# Input_-_Pedals.net
KiCad netlist of a schematic drawn in Altium Designer
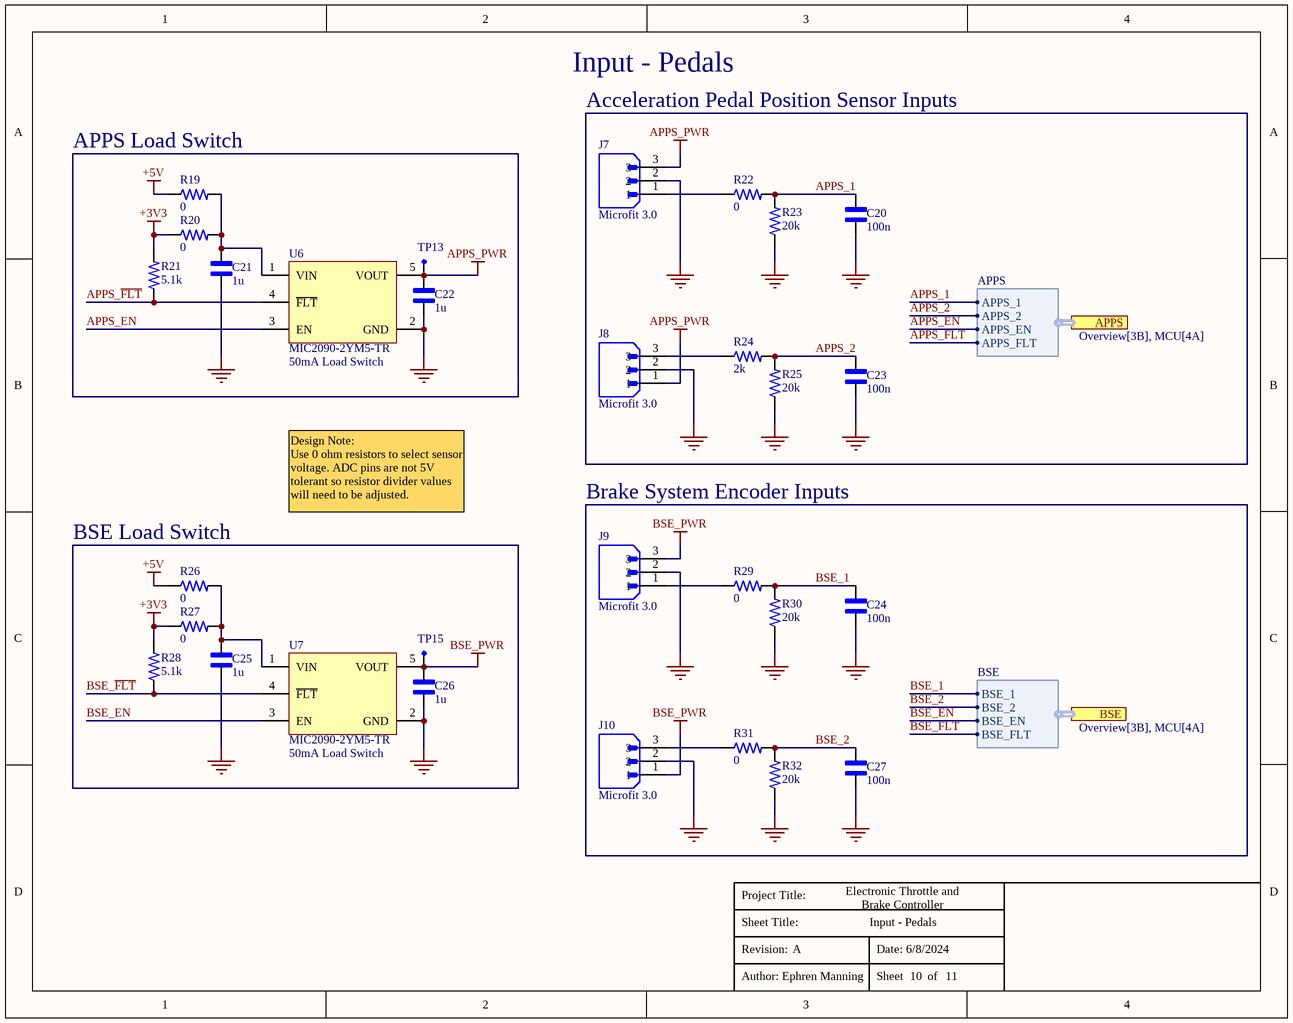
[diagram p0: Input - Pedals.SchDoc]

(export (version "E")
  (design (tool "Eeschema 10.0.6"))
  (components
    (comp (ref "C20")
      (value "100n")
      (footprint "CAP_0402-Footprint-1")
      (description "100nF 10V 10% 0402 CAP")
      (fields (field (name "DIGIKEY PART NUMBER") "1276-1002-1-ND"))
      (libsource (lib "SAE @ UIC Formula Electric") (part "CAP_0402-Symbol-1"))
    )
    (comp (ref "C21")
      (value "1u")
      (footprint "CAP_0402-Footprint-1")
      (description "1uF 10V 10% 0402 CAP")
      (fields (field (name "DIGIKEY PART NUMBER") "1276-1076-1-ND"))
      (libsource (lib "SAE @ UIC Formula Electric") (part "CAP_0402-Symbol-1"))
    )
    (comp (ref "C22")
      (value "1u")
      (footprint "CAP_0402-Footprint-1")
      (description "1uF 10V 10% 0402 CAP")
      (fields (field (name "DIGIKEY PART NUMBER") "1276-1076-1-ND"))
      (libsource (lib "SAE @ UIC Formula Electric") (part "CAP_0402-Symbol-1"))
    )
    (comp (ref "C23")
      (value "100n")
      (footprint "CAP_0402-Footprint-1")
      (description "100nF 10V 10% 0402 CAP")
      (fields (field (name "DIGIKEY PART NUMBER") "1276-1002-1-ND"))
      (libsource (lib "SAE @ UIC Formula Electric") (part "CAP_0402-Symbol-1"))
    )
    (comp (ref "C24")
      (value "100n")
      (footprint "CAP_0402-Footprint-1")
      (description "100nF 10V 10% 0402 CAP")
      (fields (field (name "DIGIKEY PART NUMBER") "1276-1002-1-ND"))
      (libsource (lib "SAE @ UIC Formula Electric") (part "CAP_0402-Symbol-1"))
    )
    (comp (ref "C25")
      (value "1u")
      (footprint "CAP_0402-Footprint-1")
      (description "1uF 10V 10% 0402 CAP")
      (fields (field (name "DIGIKEY PART NUMBER") "1276-1076-1-ND"))
      (libsource (lib "SAE @ UIC Formula Electric") (part "CAP_0402-Symbol-1"))
    )
    (comp (ref "C26")
      (value "1u")
      (footprint "CAP_0402-Footprint-1")
      (description "1uF 10V 10% 0402 CAP")
      (fields (field (name "DIGIKEY PART NUMBER") "1276-1076-1-ND"))
      (libsource (lib "SAE @ UIC Formula Electric") (part "CAP_0402-Symbol-1"))
    )
    (comp (ref "C27")
      (value "100n")
      (footprint "CAP_0402-Footprint-1")
      (description "100nF 10V 10% 0402 CAP")
      (fields (field (name "DIGIKEY PART NUMBER") "1276-1002-1-ND"))
      (libsource (lib "SAE @ UIC Formula Electric") (part "CAP_0402-Symbol-1"))
    )
    (comp (ref "J7")
      (value "Microfit 3.0")
      (footprint "MOLEX_436500316")
      (description "1x3 Gold Microfit")
      (fields (field (name "DIGIKEY PART NUMBER") "WM1923-ND"))
      (libsource (lib "SAE @ UIC Formula Electric") (part "436500316"))
    )
    (comp (ref "J8")
      (value "Microfit 3.0")
      (footprint "MOLEX_436500316")
      (description "1x3 Gold Microfit")
      (fields (field (name "DIGIKEY PART NUMBER") "WM1923-ND"))
      (libsource (lib "SAE @ UIC Formula Electric") (part "436500316"))
    )
    (comp (ref "J9")
      (value "Microfit 3.0")
      (footprint "MOLEX_436500316")
      (description "1x3 Gold Microfit")
      (fields (field (name "DIGIKEY PART NUMBER") "WM1923-ND"))
      (libsource (lib "SAE @ UIC Formula Electric") (part "436500316"))
    )
    (comp (ref "J10")
      (value "Microfit 3.0")
      (footprint "MOLEX_436500316")
      (description "1x3 Gold Microfit")
      (fields (field (name "DIGIKEY PART NUMBER") "WM1923-ND"))
      (libsource (lib "SAE @ UIC Formula Electric") (part "436500316"))
    )
    (comp (ref "R19")
      (value "0")
      (footprint "RES_0402-Footprint-1")
      (description "0 Ohm 1/16W 0402 Resistor")
      (fields (field (name "DIGIKEY PART NUMBER") "311-0.0JRCT-ND"))
      (libsource (lib "SAE @ UIC Formula Electric") (part "RES_0402_Symbol"))
    )
    (comp (ref "R20")
      (value "0")
      (footprint "RES_0402-Footprint-1")
      (description "0 Ohm 1/16W 0402 Resistor")
      (fields (field (name "DIGIKEY PART NUMBER") "311-0.0JRCT-ND"))
      (libsource (lib "SAE @ UIC Formula Electric") (part "RES_0402_Symbol"))
    )
    (comp (ref "R21")
      (value "5.1k")
      (footprint "RES_0402-Footprint-1")
      (description "5.1k 1% 1/16W 0402 Resistor")
      (fields (field (name "DIGIKEY PART NUMBER") "311-5.10KLRCT-ND"))
      (libsource (lib "SAE @ UIC Formula Electric") (part "RES_0402_Symbol"))
    )
    (comp (ref "R22")
      (value "0")
      (footprint "RES_0402-Footprint-1")
      (description "0 Ohm 1/16W 0402 Resistor")
      (fields (field (name "DIGIKEY PART NUMBER") "311-0.0JRCT-ND"))
      (libsource (lib "SAE @ UIC Formula Electric") (part "RES_0402_Symbol"))
    )
    (comp (ref "R23")
      (value "20k")
      (footprint "RES_0402-Footprint-1")
      (description "20k 0.1% 1/16W 0402 Thin Film")
      (fields (field (name "DIGIKEY PART NUMBER") "YAG1388CT-ND"))
      (libsource (lib "SAE @ UIC Formula Electric") (part "RES_0402_Symbol"))
    )
    (comp (ref "R24")
      (value "2k")
      (footprint "RES_0402-Footprint-1")
      (description "2k 0.1% 1/16W 0402 Thin Film")
      (fields (field (name "DIGIKEY PART NUMBER") "YAG2303CT-ND"))
      (libsource (lib "SAE @ UIC Formula Electric") (part "RES_0402_Symbol"))
    )
    (comp (ref "R25")
      (value "20k")
      (footprint "RES_0402-Footprint-1")
      (description "20k 0.1% 1/16W 0402 Thin Film")
      (fields (field (name "DIGIKEY PART NUMBER") "YAG1388CT-ND"))
      (libsource (lib "SAE @ UIC Formula Electric") (part "RES_0402_Symbol"))
    )
    (comp (ref "R26")
      (value "0")
      (footprint "RES_0402-Footprint-1")
      (description "0 Ohm 1/16W 0402 Resistor")
      (fields (field (name "DIGIKEY PART NUMBER") "311-0.0JRCT-ND"))
      (libsource (lib "SAE @ UIC Formula Electric") (part "RES_0402_Symbol"))
    )
    (comp (ref "R27")
      (value "0")
      (footprint "RES_0402-Footprint-1")
      (description "0 Ohm 1/16W 0402 Resistor")
      (fields (field (name "DIGIKEY PART NUMBER") "311-0.0JRCT-ND"))
      (libsource (lib "SAE @ UIC Formula Electric") (part "RES_0402_Symbol"))
    )
    (comp (ref "R28")
      (value "5.1k")
      (footprint "RES_0402-Footprint-1")
      (description "5.1k 1% 1/16W 0402 Resistor")
      (fields (field (name "DIGIKEY PART NUMBER") "311-5.10KLRCT-ND"))
      (libsource (lib "SAE @ UIC Formula Electric") (part "RES_0402_Symbol"))
    )
    (comp (ref "R29")
      (value "0")
      (footprint "RES_0402-Footprint-1")
      (description "0 Ohm 1/16W 0402 Resistor")
      (fields (field (name "DIGIKEY PART NUMBER") "311-0.0JRCT-ND"))
      (libsource (lib "SAE @ UIC Formula Electric") (part "RES_0402_Symbol"))
    )
    (comp (ref "R30")
      (value "20k")
      (footprint "RES_0402-Footprint-1")
      (description "20k 0.1% 1/16W 0402 Thin Film")
      (fields (field (name "DIGIKEY PART NUMBER") "YAG1388CT-ND"))
      (libsource (lib "SAE @ UIC Formula Electric") (part "RES_0402_Symbol"))
    )
    (comp (ref "R31")
      (value "0")
      (footprint "RES_0402-Footprint-1")
      (description "0 Ohm 1/16W 0402 Resistor")
      (fields (field (name "DIGIKEY PART NUMBER") "311-0.0JRCT-ND"))
      (libsource (lib "SAE @ UIC Formula Electric") (part "RES_0402_Symbol"))
    )
    (comp (ref "R32")
      (value "20k")
      (footprint "RES_0402-Footprint-1")
      (description "20k 0.1% 1/16W 0402 Thin Film")
      (fields (field (name "DIGIKEY PART NUMBER") "YAG1388CT-ND"))
      (libsource (lib "SAE @ UIC Formula Electric") (part "RES_0402_Symbol"))
    )
    (comp (ref "TP13")
      (value "SMD Testpoint")
      (footprint "SMD Testpoint-Footprint-1")
      (description "Flat 50x50mil Test Point")
      (libsource (lib "SAE @ UIC Formula Electric") (part "SMD Testpoint-Symbol-1"))
    )
    (comp (ref "TP15")
      (value "SMD Testpoint")
      (footprint "SMD Testpoint-Footprint-1")
      (description "Flat 50x50mil Test Point")
      (libsource (lib "SAE @ UIC Formula Electric") (part "SMD Testpoint-Symbol-1"))
    )
    (comp (ref "U6")
      (value "MIC2090-2YM5-TR")
      (footprint "SOT95P275X110-5N")
      (description "50mA Load Switch w/ Overcurrent Protection")
      (fields (field (name "DIGIKEY PART NUMBER") "576-3964-1-ND"))
      (libsource (lib "SAE @ UIC Formula Electric") (part "MIC2090-2YM5-TR-Symbol-1"))
    )
    (comp (ref "U7")
      (value "MIC2090-2YM5-TR")
      (footprint "SOT95P275X110-5N")
      (description "50mA Load Switch w/ Overcurrent Protection")
      (fields (field (name "DIGIKEY PART NUMBER") "576-3964-1-ND"))
      (libsource (lib "SAE @ UIC Formula Electric") (part "MIC2090-2YM5-TR-Symbol-1"))
    )
  )
  (nets
    (net (code "3") (name "+3V3") (class "Default")
      (node (ref "R20") (pin "1") (pinfunction "1_1") (pintype "passive"))
      (node (ref "R21") (pin "2") (pinfunction "2_2") (pintype "passive"))
      (node (ref "R27") (pin "1") (pinfunction "1_1") (pintype "passive"))
      (node (ref "R28") (pin "2") (pinfunction "2_2") (pintype "passive"))
    )
    (net (code "4") (name "+5V") (class "Default")
      (node (ref "R19") (pin "1") (pinfunction "1_1") (pintype "passive"))
      (node (ref "R26") (pin "1") (pinfunction "1_1") (pintype "passive"))
    )
    (net (code "5") (name "/APPS_1") (class "Default")
      (node (ref "C20") (pin "2") (pinfunction "2_2") (pintype "passive"))
      (node (ref "R22") (pin "2") (pinfunction "2_2") (pintype "passive"))
      (node (ref "R23") (pin "2") (pinfunction "2_2") (pintype "passive"))
    )
    (net (code "6") (name "/APPS_2") (class "Default")
      (node (ref "C23") (pin "2") (pinfunction "2_2") (pintype "passive"))
      (node (ref "R24") (pin "2") (pinfunction "2_2") (pintype "passive"))
      (node (ref "R25") (pin "2") (pinfunction "2_2") (pintype "passive"))
    )
    (net (code "7") (name "/APPS_EN") (class "Default")
      (node (ref "U6") (pin "3") (pinfunction "EN_3") (pintype "passive"))
    )
    (net (code "8") (name "/APPS_~{FLT}") (class "Default")
      (node (ref "R21") (pin "1") (pinfunction "1_1") (pintype "passive"))
      (node (ref "U6") (pin "4") (pinfunction "~{FLT}_4") (pintype "passive"))
    )
    (net (code "9") (name "/BSE_1") (class "Default")
      (node (ref "C24") (pin "2") (pinfunction "2_2") (pintype "passive"))
      (node (ref "R29") (pin "2") (pinfunction "2_2") (pintype "passive"))
      (node (ref "R30") (pin "2") (pinfunction "2_2") (pintype "passive"))
    )
    (net (code "10") (name "/BSE_2") (class "Default")
      (node (ref "C27") (pin "2") (pinfunction "2_2") (pintype "passive"))
      (node (ref "R31") (pin "2") (pinfunction "2_2") (pintype "passive"))
      (node (ref "R32") (pin "2") (pinfunction "2_2") (pintype "passive"))
    )
    (net (code "11") (name "/BSE_EN") (class "Default")
      (node (ref "U7") (pin "3") (pinfunction "EN_3") (pintype "passive"))
    )
    (net (code "12") (name "/BSE_~{FLT}") (class "Default")
      (node (ref "R28") (pin "1") (pinfunction "1_1") (pintype "passive"))
      (node (ref "U7") (pin "4") (pinfunction "~{FLT}_4") (pintype "passive"))
    )
    (net (code "15") (name "APPS_PWR") (class "Default")
      (node (ref "C22") (pin "2") (pinfunction "2_2") (pintype "passive"))
      (node (ref "J7") (pin "3") (pinfunction "3_3") (pintype "passive"))
      (node (ref "J8") (pin "1") (pinfunction "1_1") (pintype "passive"))
      (node (ref "TP13") (pin "1") (pinfunction "1_1") (pintype "passive"))
      (node (ref "U6") (pin "5") (pinfunction "VOUT_5") (pintype "passive"))
    )
    (net (code "16") (name "BSE_PWR") (class "Default")
      (node (ref "C26") (pin "2") (pinfunction "2_2") (pintype "passive"))
      (node (ref "J10") (pin "1") (pinfunction "1_1") (pintype "passive"))
      (node (ref "J9") (pin "3") (pinfunction "3_3") (pintype "passive"))
      (node (ref "TP15") (pin "1") (pinfunction "1_1") (pintype "passive"))
      (node (ref "U7") (pin "5") (pinfunction "VOUT_5") (pintype "passive"))
    )
    (net (code "17") (name "GND") (class "Default")
      (node (ref "C20") (pin "1") (pinfunction "1_1") (pintype "passive"))
      (node (ref "C21") (pin "1") (pinfunction "1_1") (pintype "passive"))
      (node (ref "C22") (pin "1") (pinfunction "1_1") (pintype "passive"))
      (node (ref "C23") (pin "1") (pinfunction "1_1") (pintype "passive"))
      (node (ref "C24") (pin "1") (pinfunction "1_1") (pintype "passive"))
      (node (ref "C25") (pin "1") (pinfunction "1_1") (pintype "passive"))
      (node (ref "C26") (pin "1") (pinfunction "1_1") (pintype "passive"))
      (node (ref "C27") (pin "1") (pinfunction "1_1") (pintype "passive"))
      (node (ref "J10") (pin "2") (pinfunction "2_2") (pintype "passive"))
      (node (ref "J7") (pin "2") (pinfunction "2_2") (pintype "passive"))
      (node (ref "J8") (pin "2") (pinfunction "2_2") (pintype "passive"))
      (node (ref "J9") (pin "2") (pinfunction "2_2") (pintype "passive"))
      (node (ref "R23") (pin "1") (pinfunction "1_1") (pintype "passive"))
      (node (ref "R25") (pin "1") (pinfunction "1_1") (pintype "passive"))
      (node (ref "R30") (pin "1") (pinfunction "1_1") (pintype "passive"))
      (node (ref "R32") (pin "1") (pinfunction "1_1") (pintype "passive"))
      (node (ref "U6") (pin "2") (pinfunction "GND_2") (pintype "passive"))
      (node (ref "U7") (pin "2") (pinfunction "GND_2") (pintype "passive"))
    )
    (net (code "18") (name "Net-(J7-Pad1)") (class "Default")
      (node (ref "J7") (pin "1") (pinfunction "1_1") (pintype "passive"))
      (node (ref "R22") (pin "1") (pinfunction "1_1") (pintype "passive"))
    )
    (net (code "19") (name "Net-(J8-Pad3)") (class "Default")
      (node (ref "J8") (pin "3") (pinfunction "3_3") (pintype "passive"))
      (node (ref "R24") (pin "1") (pinfunction "1_1") (pintype "passive"))
    )
    (net (code "20") (name "Net-(J9-Pad1)") (class "Default")
      (node (ref "J9") (pin "1") (pinfunction "1_1") (pintype "passive"))
      (node (ref "R29") (pin "1") (pinfunction "1_1") (pintype "passive"))
    )
    (net (code "21") (name "Net-(J10-Pad3)") (class "Default")
      (node (ref "J10") (pin "3") (pinfunction "3_3") (pintype "passive"))
      (node (ref "R31") (pin "1") (pinfunction "1_1") (pintype "passive"))
    )
    (net (code "22") (name "Net-(U6-VIN)") (class "Default")
      (node (ref "C21") (pin "2") (pinfunction "2_2") (pintype "passive"))
      (node (ref "R19") (pin "2") (pinfunction "2_2") (pintype "passive"))
      (node (ref "R20") (pin "2") (pinfunction "2_2") (pintype "passive"))
      (node (ref "U6") (pin "1") (pinfunction "VIN_1") (pintype "passive"))
    )
    (net (code "23") (name "Net-(U7-VIN)") (class "Default")
      (node (ref "C25") (pin "2") (pinfunction "2_2") (pintype "passive"))
      (node (ref "R26") (pin "2") (pinfunction "2_2") (pintype "passive"))
      (node (ref "R27") (pin "2") (pinfunction "2_2") (pintype "passive"))
      (node (ref "U7") (pin "1") (pinfunction "VIN_1") (pintype "passive"))
    )
  )
)
